# analog_rng2.net
KiCad netlist of a schematic drawn in EAGLE
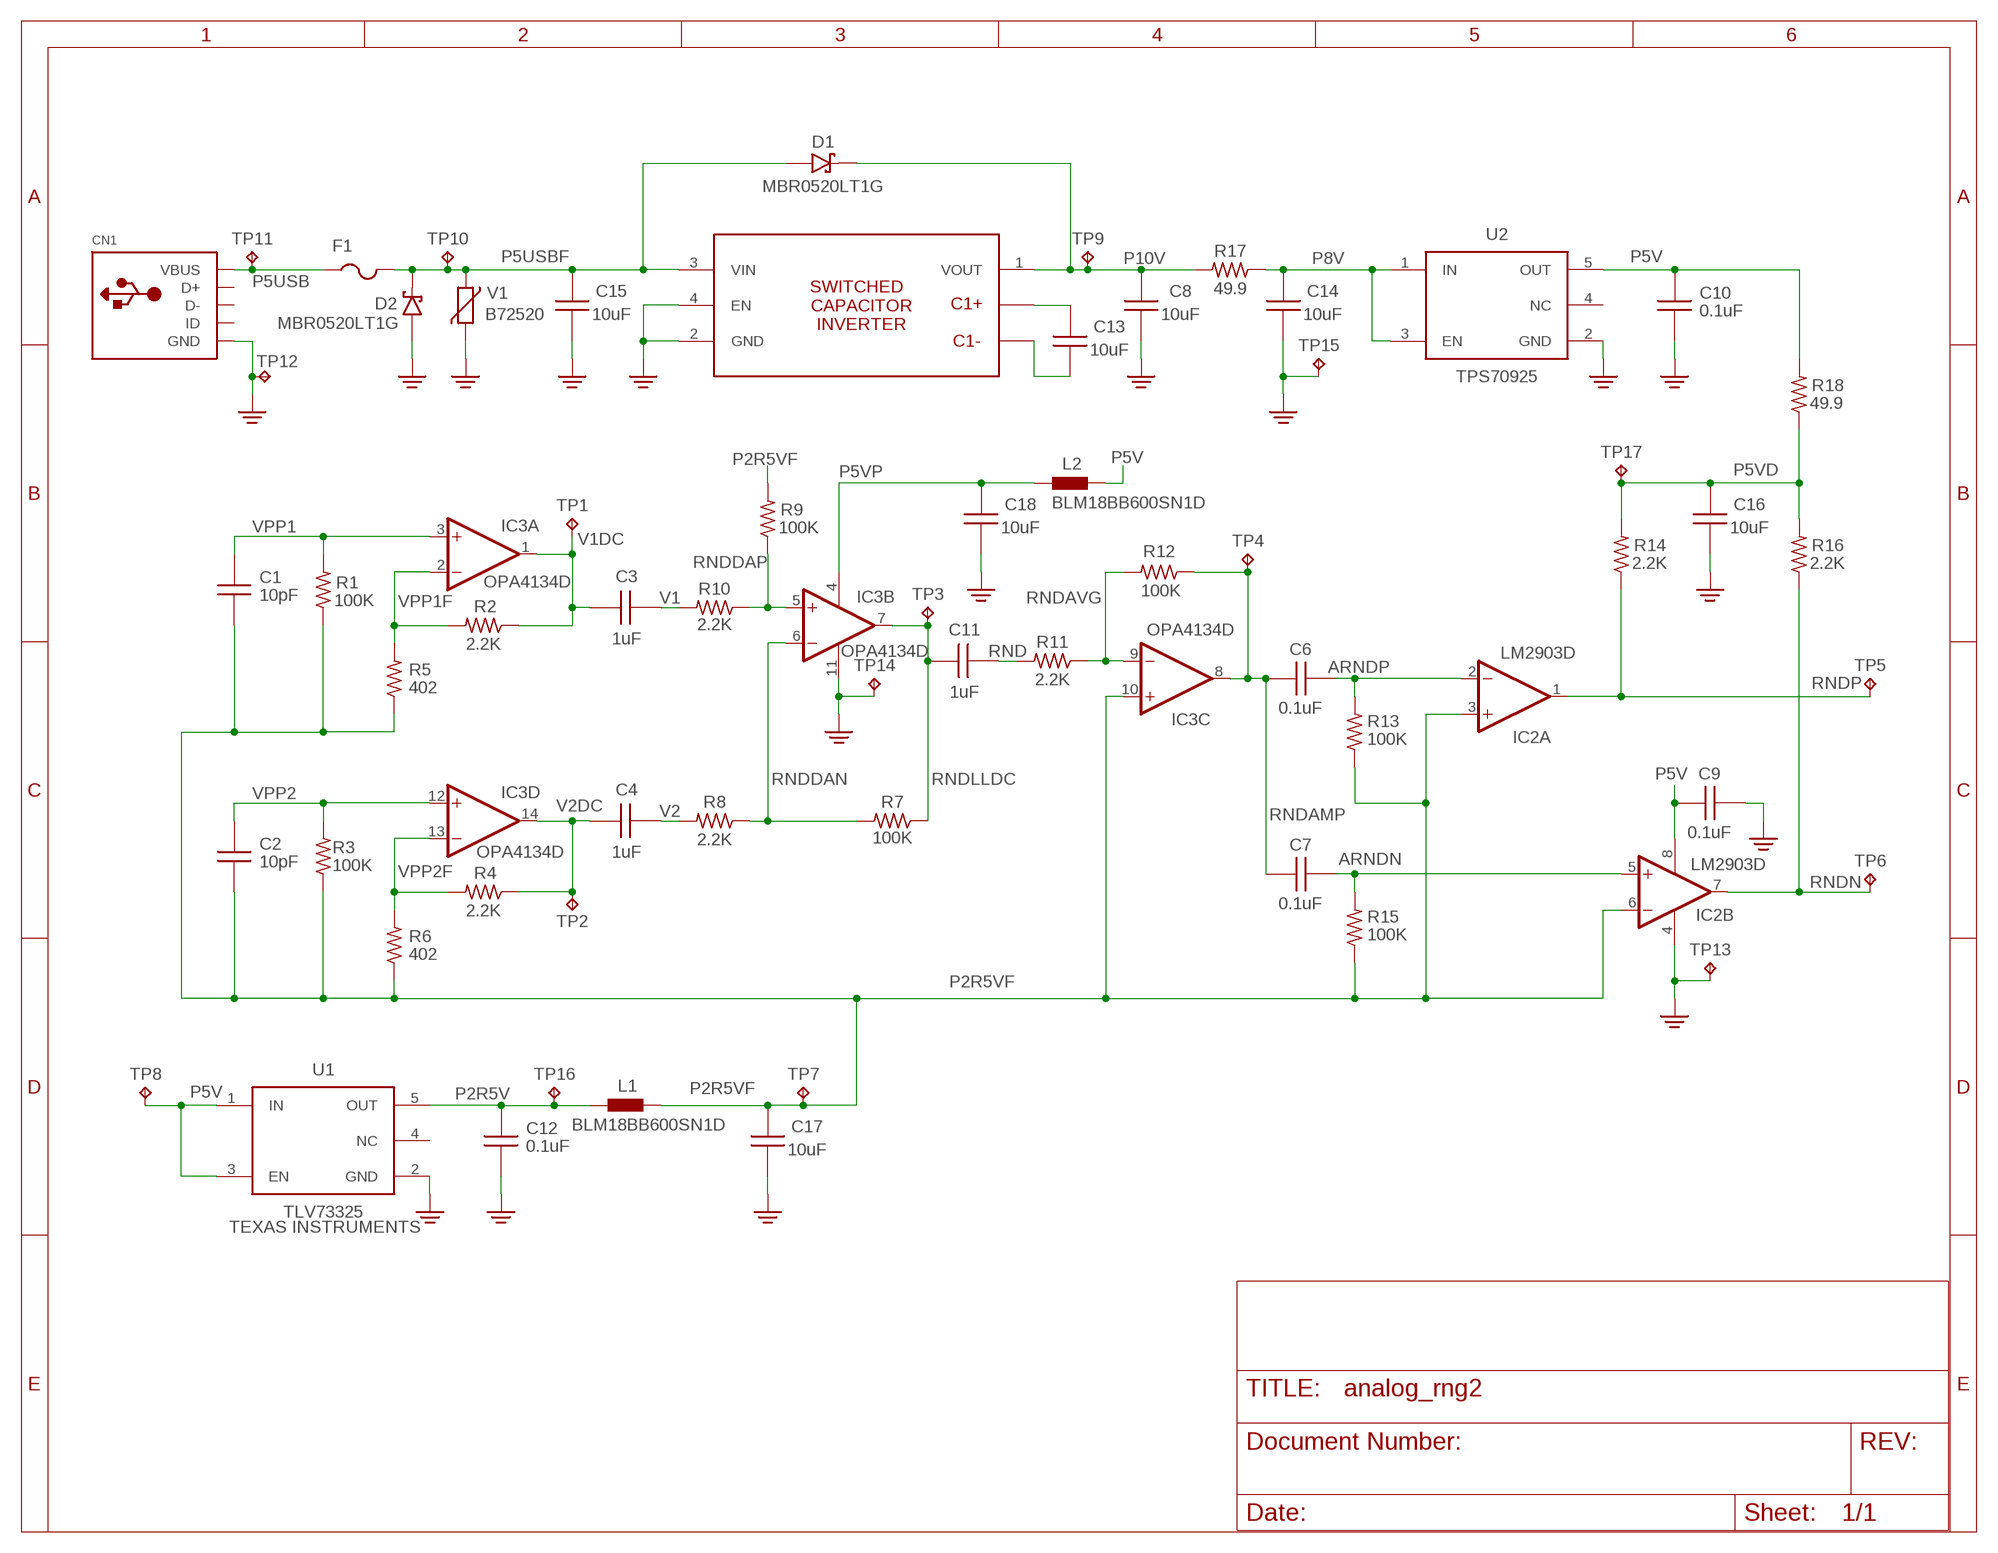
[diagram p0: schematic, sheet 1]

(export (version "E")
  (design (tool "Eeschema 10.0.6"))
  (components
    (comp (ref "C1")
      (value "10pF")
      (footprint "eagle-import:C0603")
      (libsource (lib "eagle-import") (part "C-USC0603"))
    )
    (comp (ref "C2")
      (value "10pF")
      (footprint "eagle-import:C0603")
      (libsource (lib "eagle-import") (part "C-USC0603"))
    )
    (comp (ref "C3")
      (value "1uF")
      (footprint "eagle-import:C1206")
      (libsource (lib "eagle-import") (part "C-USC1206"))
    )
    (comp (ref "C4")
      (value "1uF")
      (footprint "eagle-import:C1206")
      (libsource (lib "eagle-import") (part "C-USC1206"))
    )
    (comp (ref "C6")
      (value "0.1uF")
      (footprint "eagle-import:C0603")
      (libsource (lib "eagle-import") (part "C-USC0603"))
    )
    (comp (ref "C7")
      (value "0.1uF")
      (footprint "eagle-import:C0603")
      (libsource (lib "eagle-import") (part "C-USC0603"))
    )
    (comp (ref "C8")
      (value "10uF")
      (footprint "eagle-import:C1206")
      (libsource (lib "eagle-import") (part "C-USC1206"))
    )
    (comp (ref "C9")
      (value "0.1uF")
      (footprint "eagle-import:C0603")
      (libsource (lib "eagle-import") (part "C-USC0603"))
    )
    (comp (ref "C10")
      (value "0.1uF")
      (footprint "eagle-import:C0603")
      (libsource (lib "eagle-import") (part "C-USC0603"))
    )
    (comp (ref "C11")
      (value "1uF")
      (footprint "eagle-import:C1206")
      (libsource (lib "eagle-import") (part "C-USC1206"))
    )
    (comp (ref "C12")
      (value "0.1uF")
      (footprint "eagle-import:C0603")
      (libsource (lib "eagle-import") (part "C-USC0603"))
    )
    (comp (ref "C13")
      (value "10uF")
      (footprint "eagle-import:C1206")
      (libsource (lib "eagle-import") (part "C-USC1206"))
    )
    (comp (ref "C14")
      (value "10uF")
      (footprint "eagle-import:C1206")
      (libsource (lib "eagle-import") (part "C-USC1206"))
    )
    (comp (ref "C15")
      (value "10uF")
      (footprint "eagle-import:C1206")
      (libsource (lib "eagle-import") (part "C-USC1206"))
    )
    (comp (ref "C16")
      (value "10uF")
      (footprint "eagle-import:C1206")
      (libsource (lib "eagle-import") (part "C-USC1206"))
    )
    (comp (ref "C17")
      (value "10uF")
      (footprint "eagle-import:C1206")
      (libsource (lib "eagle-import") (part "C-USC1206"))
    )
    (comp (ref "C18")
      (value "10uF")
      (footprint "eagle-import:C1206")
      (libsource (lib "eagle-import") (part "C-USC1206"))
    )
    (comp (ref "CN1")
      (value "USBMINIB")
      (footprint "eagle-import:USB-MINIB")
      (libsource (lib "eagle-import") (part "USBMINIB"))
    )
    (comp (ref "D1")
      (value "MBR0520LT1G")
      (footprint "eagle-import:SOD-123")
      (libsource (lib "eagle-import") (part "MBR0520LT1GSOD-123"))
    )
    (comp (ref "D2")
      (value "MBR0520LT1G")
      (footprint "eagle-import:SOD-123")
      (libsource (lib "eagle-import") (part "MBR0520LT1GSOD-123"))
    )
    (comp (ref "F1")
      (value "PTCFUSE-1812")
      (footprint "eagle-import:1812")
      (libsource (lib "eagle-import") (part "PTCFUSE-1812"))
    )
    (comp (ref "IC2")
      (value "LM2903D")
      (footprint "eagle-import:SO08")
      (libsource (lib "eagle-import") (part "LM2903D"))
    )
    (comp (ref "IC3")
      (value "OPA4134D")
      (footprint "eagle-import:SO14")
      (fields (field (name "MF") "TEXAS INSTRUMENTS") (field (name "MPN") "OPA4134UA/2K5"))
      (libsource (lib "eagle-import") (part "OPA4134D"))
    )
    (comp (ref "L1")
      (value "BLM18BB600SN1D")
      (footprint "eagle-import:R0805")
      (libsource (lib "eagle-import") (part "BEADR0805"))
    )
    (comp (ref "L2")
      (value "BLM18BB600SN1D")
      (footprint "eagle-import:R0805")
      (libsource (lib "eagle-import") (part "BEADR0805"))
    )
    (comp (ref "R1")
      (value "100K")
      (footprint "eagle-import:R1206")
      (libsource (lib "eagle-import") (part "R-US_R1206"))
    )
    (comp (ref "R2")
      (value "2.2K")
      (footprint "eagle-import:R1206")
      (libsource (lib "eagle-import") (part "R-US_R1206"))
    )
    (comp (ref "R3")
      (value "100K")
      (footprint "eagle-import:R1206")
      (libsource (lib "eagle-import") (part "R-US_R1206"))
    )
    (comp (ref "R4")
      (value "2.2K")
      (footprint "eagle-import:R1206")
      (libsource (lib "eagle-import") (part "R-US_R1206"))
    )
    (comp (ref "R5")
      (value "402")
      (footprint "eagle-import:R1206")
      (libsource (lib "eagle-import") (part "R-US_R1206"))
    )
    (comp (ref "R6")
      (value "402")
      (footprint "eagle-import:R1206")
      (libsource (lib "eagle-import") (part "R-US_R1206"))
    )
    (comp (ref "R7")
      (value "100K")
      (footprint "eagle-import:R1206")
      (libsource (lib "eagle-import") (part "R-US_R1206"))
    )
    (comp (ref "R8")
      (value "2.2K")
      (footprint "eagle-import:R1206")
      (libsource (lib "eagle-import") (part "R-US_R1206"))
    )
    (comp (ref "R9")
      (value "100K")
      (footprint "eagle-import:R1206")
      (libsource (lib "eagle-import") (part "R-US_R1206"))
    )
    (comp (ref "R10")
      (value "2.2K")
      (footprint "eagle-import:R1206")
      (libsource (lib "eagle-import") (part "R-US_R1206"))
    )
    (comp (ref "R11")
      (value "2.2K")
      (footprint "eagle-import:R1206")
      (libsource (lib "eagle-import") (part "R-US_R1206"))
    )
    (comp (ref "R12")
      (value "100K")
      (footprint "eagle-import:R1206")
      (libsource (lib "eagle-import") (part "R-US_R1206"))
    )
    (comp (ref "R13")
      (value "100K")
      (footprint "eagle-import:R1206")
      (libsource (lib "eagle-import") (part "R-US_R1206"))
    )
    (comp (ref "R14")
      (value "2.2K")
      (footprint "eagle-import:R1206")
      (libsource (lib "eagle-import") (part "R-US_R1206"))
    )
    (comp (ref "R15")
      (value "100K")
      (footprint "eagle-import:R1206")
      (libsource (lib "eagle-import") (part "R-US_R1206"))
    )
    (comp (ref "R16")
      (value "2.2K")
      (footprint "eagle-import:R1206")
      (libsource (lib "eagle-import") (part "R-US_R1206"))
    )
    (comp (ref "R17")
      (value "49.9")
      (footprint "eagle-import:R1206")
      (libsource (lib "eagle-import") (part "R-US_R1206"))
    )
    (comp (ref "R18")
      (value "49.9")
      (footprint "eagle-import:R1206")
      (libsource (lib "eagle-import") (part "R-US_R1206"))
    )
    (comp (ref "TP1")
      (value "TPPAD1-20")
      (footprint "eagle-import:P1-20")
      (libsource (lib "eagle-import") (part "TPPAD1-20"))
    )
    (comp (ref "TP2")
      (value "TPPAD1-20")
      (footprint "eagle-import:P1-20")
      (libsource (lib "eagle-import") (part "TPPAD1-20"))
    )
    (comp (ref "TP3")
      (value "TPPAD1-20")
      (footprint "eagle-import:P1-20")
      (libsource (lib "eagle-import") (part "TPPAD1-20"))
    )
    (comp (ref "TP4")
      (value "TPPAD1-20")
      (footprint "eagle-import:P1-20")
      (libsource (lib "eagle-import") (part "TPPAD1-20"))
    )
    (comp (ref "TP5")
      (value "TPPAD1-20")
      (footprint "eagle-import:P1-20")
      (libsource (lib "eagle-import") (part "TPPAD1-20"))
    )
    (comp (ref "TP6")
      (value "TPPAD1-20")
      (footprint "eagle-import:P1-20")
      (libsource (lib "eagle-import") (part "TPPAD1-20"))
    )
    (comp (ref "TP7")
      (value "TPPAD1-20")
      (footprint "eagle-import:P1-20")
      (libsource (lib "eagle-import") (part "TPPAD1-20"))
    )
    (comp (ref "TP8")
      (value "TPPAD1-20")
      (footprint "eagle-import:P1-20")
      (libsource (lib "eagle-import") (part "TPPAD1-20"))
    )
    (comp (ref "TP9")
      (value "TPPAD1-20")
      (footprint "eagle-import:P1-20")
      (libsource (lib "eagle-import") (part "TPPAD1-20"))
    )
    (comp (ref "TP10")
      (value "TPPAD1-20")
      (footprint "eagle-import:P1-20")
      (libsource (lib "eagle-import") (part "TPPAD1-20"))
    )
    (comp (ref "TP11")
      (value "TPPAD1-20")
      (footprint "eagle-import:P1-20")
      (libsource (lib "eagle-import") (part "TPPAD1-20"))
    )
    (comp (ref "TP12")
      (value "TPPAD1-20")
      (footprint "eagle-import:P1-20")
      (libsource (lib "eagle-import") (part "TPPAD1-20"))
    )
    (comp (ref "TP13")
      (value "TPPAD1-20")
      (footprint "eagle-import:P1-20")
      (libsource (lib "eagle-import") (part "TPPAD1-20"))
    )
    (comp (ref "TP14")
      (value "TPPAD1-20")
      (footprint "eagle-import:P1-20")
      (libsource (lib "eagle-import") (part "TPPAD1-20"))
    )
    (comp (ref "TP15")
      (value "TPPAD1-20")
      (footprint "eagle-import:P1-20")
      (libsource (lib "eagle-import") (part "TPPAD1-20"))
    )
    (comp (ref "TP16")
      (value "TPPAD1-20")
      (footprint "eagle-import:P1-20")
      (libsource (lib "eagle-import") (part "TPPAD1-20"))
    )
    (comp (ref "TP17")
      (value "TPPAD1-20")
      (footprint "eagle-import:P1-20")
      (libsource (lib "eagle-import") (part "TPPAD1-20"))
    )
    (comp (ref "U1")
      (value "TLV73325")
      (footprint "eagle-import:SOT23-5")
      (fields (field (name "MF") "TEXAS INSTRUMENTS") (field (name "MPN") "TLV73325PDBVT"))
      (libsource (lib "eagle-import") (part "TLV73325"))
    )
    (comp (ref "U2")
      (value "TPS70925")
      (footprint "eagle-import:SOT23-5")
      (fields (field (name "MF") "TEXAS INSTRUMENTS") (field (name "MPN") "TLV70950DBVR"))
      (libsource (lib "eagle-import") (part "TPS70925"))
    )
    (comp (ref "U23423")
      (value "LM277625")
      (footprint "eagle-import:SOT23-6")
      (fields (field (name "MF") "TEXAS INSTRUMENTS") (field (name "MPN") "LM2776DBVR"))
      (libsource (lib "eagle-import") (part "LM277625"))
    )
    (comp (ref "V1")
      (value "B72520")
      (footprint "eagle-import:CT_CN1206")
      (libsource (lib "eagle-import") (part "VARISTORCN1206"))
    )
  )
  (nets
    (net (code "1") (name "/ARNDN") (class "Default")
      (node (ref "C7") (pin "2") (pinfunction "2_2") (pintype "passive"))
      (node (ref "IC2") (pin "5") (pinfunction "+IN_5") (pintype "input"))
      (node (ref "R15") (pin "2") (pinfunction "2_2") (pintype "passive"))
    )
    (net (code "2") (name "/ARNDP") (class "Default")
      (node (ref "C6") (pin "2") (pinfunction "2_2") (pintype "passive"))
      (node (ref "IC2") (pin "2") (pinfunction "-IN_2") (pintype "input"))
      (node (ref "R13") (pin "2") (pinfunction "2_2") (pintype "passive"))
    )
    (net (code "3") (name "/P2R5V") (class "Default")
      (node (ref "C12") (pin "1") (pinfunction "1_1") (pintype "passive"))
      (node (ref "L1") (pin "1") (pinfunction "1_1") (pintype "passive"))
      (node (ref "TP16") (pin "TP") (pinfunction "TP_TP") (pintype "input"))
      (node (ref "U1") (pin "5") (pinfunction "OUT_5") (pintype "power_in"))
    )
    (net (code "4") (name "/P2R5VF") (class "Default")
      (node (ref "C1") (pin "2") (pinfunction "2_2") (pintype "passive"))
      (node (ref "C17") (pin "1") (pinfunction "1_1") (pintype "passive"))
      (node (ref "C2") (pin "2") (pinfunction "2_2") (pintype "passive"))
      (node (ref "IC2") (pin "3") (pinfunction "+IN_3") (pintype "input"))
      (node (ref "IC2") (pin "6") (pinfunction "-IN_6") (pintype "input"))
      (node (ref "IC3") (pin "10") (pinfunction "+IN_10") (pintype "input"))
      (node (ref "L1") (pin "2") (pinfunction "2_2") (pintype "passive"))
      (node (ref "R1") (pin "1") (pinfunction "1_1") (pintype "passive"))
      (node (ref "R13") (pin "1") (pinfunction "1_1") (pintype "passive"))
      (node (ref "R15") (pin "1") (pinfunction "1_1") (pintype "passive"))
      (node (ref "R3") (pin "1") (pinfunction "1_1") (pintype "passive"))
      (node (ref "R5") (pin "1") (pinfunction "1_1") (pintype "passive"))
      (node (ref "R6") (pin "1") (pinfunction "1_1") (pintype "passive"))
      (node (ref "R9") (pin "2") (pinfunction "2_2") (pintype "passive"))
      (node (ref "TP7") (pin "TP") (pinfunction "TP_TP") (pintype "input"))
    )
    (net (code "5") (name "/P5USB") (class "Default")
      (node (ref "CN1") (pin "VBUS") (pinfunction "VBUS_VBUS") (pintype "power_in"))
      (node (ref "F1") (pin "1") (pinfunction "1_1") (pintype "passive"))
      (node (ref "TP11") (pin "TP") (pinfunction "TP_TP") (pintype "input"))
    )
    (net (code "6") (name "/P5USBF") (class "Default")
      (node (ref "C15") (pin "1") (pinfunction "1_1") (pintype "passive"))
      (node (ref "D1") (pin "A") (pinfunction "A_A") (pintype "passive"))
      (node (ref "D2") (pin "K") (pinfunction "K_K") (pintype "passive"))
      (node (ref "F1") (pin "2") (pinfunction "2_2") (pintype "passive"))
      (node (ref "TP10") (pin "TP") (pinfunction "TP_TP") (pintype "input"))
      (node (ref "U23423") (pin "3") (pinfunction "VIN_3") (pintype "bidirectional"))
      (node (ref "V1") (pin "1") (pinfunction "1_1") (pintype "passive"))
    )
    (net (code "7") (name "/P5V") (class "Default")
      (node (ref "C10") (pin "1") (pinfunction "1_1") (pintype "passive"))
      (node (ref "C9") (pin "1") (pinfunction "1_1") (pintype "passive"))
      (node (ref "IC2") (pin "8") (pinfunction "V+_8") (pintype "power_in"))
      (node (ref "L2") (pin "2") (pinfunction "2_2") (pintype "passive"))
      (node (ref "R18") (pin "2") (pinfunction "2_2") (pintype "passive"))
      (node (ref "TP8") (pin "TP") (pinfunction "TP_TP") (pintype "input"))
      (node (ref "U1") (pin "1") (pinfunction "IN_1") (pintype "power_in"))
      (node (ref "U1") (pin "3") (pinfunction "EN_3") (pintype "input"))
      (node (ref "U2") (pin "5") (pinfunction "OUT_5") (pintype "power_in"))
    )
    (net (code "8") (name "/P5VD") (class "Default")
      (node (ref "C16") (pin "1") (pinfunction "1_1") (pintype "passive"))
      (node (ref "R14") (pin "2") (pinfunction "2_2") (pintype "passive"))
      (node (ref "R16") (pin "2") (pinfunction "2_2") (pintype "passive"))
      (node (ref "R18") (pin "1") (pinfunction "1_1") (pintype "passive"))
      (node (ref "TP17") (pin "TP") (pinfunction "TP_TP") (pintype "input"))
    )
    (net (code "9") (name "/P5VP") (class "Default")
      (node (ref "C18") (pin "1") (pinfunction "1_1") (pintype "passive"))
      (node (ref "IC3") (pin "4") (pinfunction "V+_4") (pintype "power_in"))
      (node (ref "L2") (pin "1") (pinfunction "1_1") (pintype "passive"))
    )
    (net (code "10") (name "/P8V") (class "Default")
      (node (ref "C14") (pin "1") (pinfunction "1_1") (pintype "passive"))
      (node (ref "R17") (pin "1") (pinfunction "1_1") (pintype "passive"))
      (node (ref "U2") (pin "1") (pinfunction "IN_1") (pintype "power_in"))
      (node (ref "U2") (pin "3") (pinfunction "EN_3") (pintype "input"))
    )
    (net (code "11") (name "/P10V") (class "Default")
      (node (ref "C8") (pin "1") (pinfunction "1_1") (pintype "passive"))
      (node (ref "D1") (pin "K") (pinfunction "K_K") (pintype "passive"))
      (node (ref "R17") (pin "2") (pinfunction "2_2") (pintype "passive"))
      (node (ref "TP9") (pin "TP") (pinfunction "TP_TP") (pintype "input"))
      (node (ref "U23423") (pin "1") (pinfunction "VOUT_1") (pintype "bidirectional"))
    )
    (net (code "12") (name "/RND") (class "Default")
      (node (ref "C11") (pin "2") (pinfunction "2_2") (pintype "passive"))
      (node (ref "R11") (pin "2") (pinfunction "2_2") (pintype "passive"))
    )
    (net (code "13") (name "/RNDAMP") (class "Default")
      (node (ref "C6") (pin "1") (pinfunction "1_1") (pintype "passive"))
      (node (ref "C7") (pin "1") (pinfunction "1_1") (pintype "passive"))
      (node (ref "IC3") (pin "8") (pinfunction "OUT_8") (pintype "output"))
      (node (ref "R12") (pin "1") (pinfunction "1_1") (pintype "passive"))
      (node (ref "TP4") (pin "TP") (pinfunction "TP_TP") (pintype "input"))
    )
    (net (code "14") (name "/RNDAVG") (class "Default")
      (node (ref "IC3") (pin "9") (pinfunction "-IN_9") (pintype "input"))
      (node (ref "R11") (pin "1") (pinfunction "1_1") (pintype "passive"))
      (node (ref "R12") (pin "2") (pinfunction "2_2") (pintype "passive"))
    )
    (net (code "15") (name "/RNDDAN") (class "Default")
      (node (ref "IC3") (pin "6") (pinfunction "-IN_6") (pintype "input"))
      (node (ref "R7") (pin "2") (pinfunction "2_2") (pintype "passive"))
      (node (ref "R8") (pin "1") (pinfunction "1_1") (pintype "passive"))
    )
    (net (code "16") (name "/RNDDAP") (class "Default")
      (node (ref "IC3") (pin "5") (pinfunction "+IN_5") (pintype "input"))
      (node (ref "R10") (pin "1") (pinfunction "1_1") (pintype "passive"))
      (node (ref "R9") (pin "1") (pinfunction "1_1") (pintype "passive"))
    )
    (net (code "17") (name "/RNDLLDC") (class "Default")
      (node (ref "C11") (pin "1") (pinfunction "1_1") (pintype "passive"))
      (node (ref "IC3") (pin "7") (pinfunction "OUT_7") (pintype "output"))
      (node (ref "R7") (pin "1") (pinfunction "1_1") (pintype "passive"))
      (node (ref "TP3") (pin "TP") (pinfunction "TP_TP") (pintype "input"))
    )
    (net (code "18") (name "/RNDN") (class "Default")
      (node (ref "IC2") (pin "7") (pinfunction "OUT_7") (pintype "output"))
      (node (ref "R16") (pin "1") (pinfunction "1_1") (pintype "passive"))
      (node (ref "TP6") (pin "TP") (pinfunction "TP_TP") (pintype "input"))
    )
    (net (code "19") (name "/RNDP") (class "Default")
      (node (ref "IC2") (pin "1") (pinfunction "OUT_1") (pintype "output"))
      (node (ref "R14") (pin "1") (pinfunction "1_1") (pintype "passive"))
      (node (ref "TP5") (pin "TP") (pinfunction "TP_TP") (pintype "input"))
    )
    (net (code "20") (name "/V1") (class "Default")
      (node (ref "C3") (pin "2") (pinfunction "2_2") (pintype "passive"))
      (node (ref "R10") (pin "2") (pinfunction "2_2") (pintype "passive"))
    )
    (net (code "21") (name "/V1DC") (class "Default")
      (node (ref "C3") (pin "1") (pinfunction "1_1") (pintype "passive"))
      (node (ref "IC3") (pin "1") (pinfunction "OUT_1") (pintype "output"))
      (node (ref "R2") (pin "1") (pinfunction "1_1") (pintype "passive"))
      (node (ref "TP1") (pin "TP") (pinfunction "TP_TP") (pintype "input"))
    )
    (net (code "22") (name "/V2") (class "Default")
      (node (ref "C4") (pin "2") (pinfunction "2_2") (pintype "passive"))
      (node (ref "R8") (pin "2") (pinfunction "2_2") (pintype "passive"))
    )
    (net (code "23") (name "/V2DC") (class "Default")
      (node (ref "C4") (pin "1") (pinfunction "1_1") (pintype "passive"))
      (node (ref "IC3") (pin "14") (pinfunction "OUT_14") (pintype "output"))
      (node (ref "R4") (pin "1") (pinfunction "1_1") (pintype "passive"))
      (node (ref "TP2") (pin "TP") (pinfunction "TP_TP") (pintype "input"))
    )
    (net (code "24") (name "/VPP1") (class "Default")
      (node (ref "C1") (pin "1") (pinfunction "1_1") (pintype "passive"))
      (node (ref "IC3") (pin "3") (pinfunction "+IN_3") (pintype "input"))
      (node (ref "R1") (pin "2") (pinfunction "2_2") (pintype "passive"))
    )
    (net (code "25") (name "/VPP1F") (class "Default")
      (node (ref "IC3") (pin "2") (pinfunction "-IN_2") (pintype "input"))
      (node (ref "R2") (pin "2") (pinfunction "2_2") (pintype "passive"))
      (node (ref "R5") (pin "2") (pinfunction "2_2") (pintype "passive"))
    )
    (net (code "26") (name "/VPP2") (class "Default")
      (node (ref "C2") (pin "1") (pinfunction "1_1") (pintype "passive"))
      (node (ref "IC3") (pin "12") (pinfunction "+IN_12") (pintype "input"))
      (node (ref "R3") (pin "2") (pinfunction "2_2") (pintype "passive"))
    )
    (net (code "27") (name "/VPP2F") (class "Default")
      (node (ref "IC3") (pin "13") (pinfunction "-IN_13") (pintype "input"))
      (node (ref "R4") (pin "2") (pinfunction "2_2") (pintype "passive"))
      (node (ref "R6") (pin "2") (pinfunction "2_2") (pintype "passive"))
    )
    (net (code "28") (name "Net-(U23423-C1N)") (class "Default")
      (node (ref "C13") (pin "2") (pinfunction "2_2") (pintype "passive"))
      (node (ref "U23423") (pin "6") (pinfunction "C1N_6") (pintype "bidirectional"))
    )
    (net (code "29") (name "Net-(U23423-C1P)") (class "Default")
      (node (ref "C13") (pin "1") (pinfunction "1_1") (pintype "passive"))
      (node (ref "U23423") (pin "5") (pinfunction "C1P_5") (pintype "bidirectional"))
    )
    (net (code "30") (name "PE") (class "Default")
      (node (ref "C10") (pin "2") (pinfunction "2_2") (pintype "passive"))
      (node (ref "C12") (pin "2") (pinfunction "2_2") (pintype "passive"))
      (node (ref "C14") (pin "2") (pinfunction "2_2") (pintype "passive"))
      (node (ref "C15") (pin "2") (pinfunction "2_2") (pintype "passive"))
      (node (ref "C16") (pin "2") (pinfunction "2_2") (pintype "passive"))
      (node (ref "C17") (pin "2") (pinfunction "2_2") (pintype "passive"))
      (node (ref "C18") (pin "2") (pinfunction "2_2") (pintype "passive"))
      (node (ref "C8") (pin "2") (pinfunction "2_2") (pintype "passive"))
      (node (ref "C9") (pin "2") (pinfunction "2_2") (pintype "passive"))
      (node (ref "CN1") (pin "GND") (pinfunction "GND_GND") (pintype "power_in"))
      (node (ref "D2") (pin "A") (pinfunction "A_A") (pintype "passive"))
      (node (ref "IC2") (pin "4") (pinfunction "V-_4") (pintype "power_in"))
      (node (ref "IC3") (pin "11") (pinfunction "V-_11") (pintype "power_in"))
      (node (ref "TP12") (pin "TP") (pinfunction "TP_TP") (pintype "input"))
      (node (ref "TP13") (pin "TP") (pinfunction "TP_TP") (pintype "input"))
      (node (ref "TP14") (pin "TP") (pinfunction "TP_TP") (pintype "input"))
      (node (ref "TP15") (pin "TP") (pinfunction "TP_TP") (pintype "input"))
      (node (ref "U1") (pin "2") (pinfunction "GND_2") (pintype "power_in"))
      (node (ref "U2") (pin "2") (pinfunction "GND_2") (pintype "power_in"))
      (node (ref "U23423") (pin "2") (pinfunction "GND_2") (pintype "bidirectional"))
      (node (ref "U23423") (pin "4") (pinfunction "EN_4") (pintype "bidirectional"))
      (node (ref "V1") (pin "2") (pinfunction "2_2") (pintype "passive"))
    )
    (net (code "31") (name "unconnected-(CN1-PadD+)") (class "Default")
      (node (ref "CN1") (pin "D+") (pinfunction "D+_D+") (pintype "bidirectional"))
    )
    (net (code "32") (name "unconnected-(CN1-PadD-)") (class "Default")
      (node (ref "CN1") (pin "D-") (pinfunction "D-_D-") (pintype "bidirectional"))
    )
    (net (code "33") (name "unconnected-(CN1-PadID)") (class "Default")
      (node (ref "CN1") (pin "ID") (pinfunction "ID_ID") (pintype "bidirectional"))
    )
    (net (code "34") (name "unconnected-(U1-NC-Pad4)") (class "Default")
      (node (ref "U1") (pin "4") (pinfunction "NC_4") (pintype "no_connect"))
    )
    (net (code "35") (name "unconnected-(U2-NC-Pad4)") (class "Default")
      (node (ref "U2") (pin "4") (pinfunction "NC_4") (pintype "no_connect"))
    )
  )
)
